# ESP01_SMD_0603.net
KiCad netlist of a schematic drawn in EAGLE
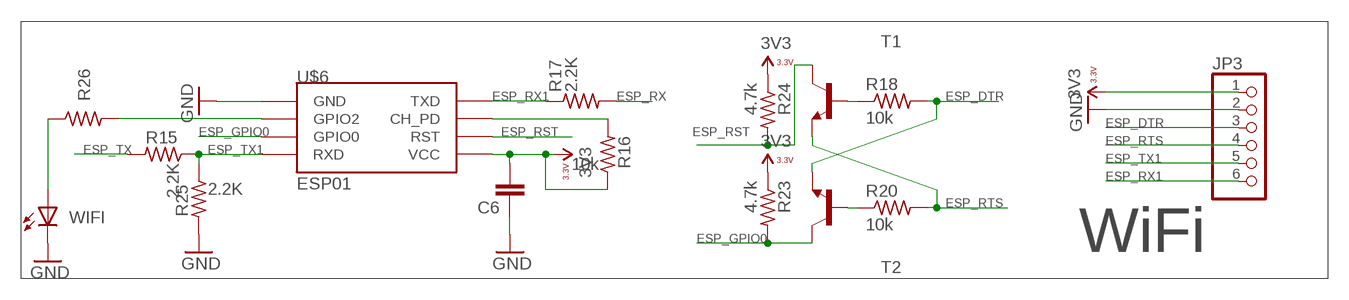
[diagram p0: schematic, sheet 1]

(export (version "E")
  (design (tool "Eeschema 10.0.6"))
  (components
    (comp (ref "C6")
      (value "C-EU050-024X044")
      (footprint "eagle-import:C050-024X044")
      (libsource (lib "eagle-import") (part "C-EU050-024X044"))
    )
    (comp (ref "JP3")
      (value "PINHD-1X6")
      (footprint "eagle-import:1X06")
      (libsource (lib "eagle-import") (part "PINHD-1X6"))
    )
    (comp (ref "R15")
      (value "2.2K")
      (footprint "eagle-import:R0603")
      (libsource (lib "eagle-import") (part "R-US_R0603"))
    )
    (comp (ref "R16")
      (value "10k")
      (footprint "eagle-import:R0603")
      (libsource (lib "eagle-import") (part "R-US_R0603"))
    )
    (comp (ref "R17")
      (value "2.2K")
      (footprint "eagle-import:R0603")
      (libsource (lib "eagle-import") (part "R-US_R0603"))
    )
    (comp (ref "R18")
      (value "10k")
      (footprint "eagle-import:R0603")
      (libsource (lib "eagle-import") (part "R-US_R0603"))
    )
    (comp (ref "R20")
      (value "10k")
      (footprint "eagle-import:R0603")
      (libsource (lib "eagle-import") (part "R-US_R0603"))
    )
    (comp (ref "R23")
      (value "4.7k")
      (footprint "eagle-import:R0603")
      (libsource (lib "eagle-import") (part "R-US_R0603"))
    )
    (comp (ref "R24")
      (value "4.7k")
      (footprint "eagle-import:R0603")
      (libsource (lib "eagle-import") (part "R-US_R0603"))
    )
    (comp (ref "R25")
      (value "2.2K")
      (footprint "eagle-import:R0603")
      (libsource (lib "eagle-import") (part "R-US_R0603"))
    )
    (comp (ref "R26")
      (value "R-US_R0603")
      (footprint "eagle-import:R0603")
      (libsource (lib "eagle-import") (part "R-US_R0603"))
    )
    (comp (ref "T1")
      (value "MMBT2222ALT1-NPN-SOT23-BEC")
      (footprint "eagle-import:SOT23-BEC")
      (libsource (lib "eagle-import") (part "-NPN-SOT23-BECMMBT2222ALT1"))
    )
    (comp (ref "T2")
      (value "MMBT2222ALT1-NPN-SOT23-BEC")
      (footprint "eagle-import:SOT23-BEC")
      (libsource (lib "eagle-import") (part "-NPN-SOT23-BECMMBT2222ALT1"))
    )
    (comp (ref "U$6")
      (value "ESP01")
      (footprint "eagle-import:ESP01")
      (libsource (lib "eagle-import") (part "ESP01"))
    )
    (comp (ref "WIFI")
      (value "LEDCHIPLED_0603")
      (footprint "eagle-import:CHIPLED_0603")
      (libsource (lib "eagle-import") (part "LEDCHIPLED_0603"))
    )
  )
  (nets
    (net (code "1") (name "/ESP_DTR") (class "Default")
      (node (ref "JP3") (pin "3") (pinfunction "3_3") (pintype "passive"))
      (node (ref "R18") (pin "2") (pinfunction "2_2") (pintype "passive"))
      (node (ref "T2") (pin "E") (pinfunction "E_E") (pintype "passive"))
    )
    (net (code "2") (name "/ESP_GPIO0") (class "Default")
      (node (ref "R23") (pin "2") (pinfunction "2_2") (pintype "passive"))
      (node (ref "T2") (pin "C") (pinfunction "C_C") (pintype "passive"))
      (node (ref "U$6") (pin "GPIO0") (pinfunction "GPIO0_GPIO0") (pintype "bidirectional"))
    )
    (net (code "3") (name "/ESP_RST") (class "Default")
      (node (ref "R24") (pin "2") (pinfunction "2_2") (pintype "passive"))
      (node (ref "T1") (pin "C") (pinfunction "C_C") (pintype "passive"))
      (node (ref "U$6") (pin "RST") (pinfunction "RST_RST") (pintype "bidirectional"))
    )
    (net (code "4") (name "/ESP_RTS") (class "Default")
      (node (ref "JP3") (pin "4") (pinfunction "4_4") (pintype "passive"))
      (node (ref "R20") (pin "2") (pinfunction "2_2") (pintype "passive"))
      (node (ref "T1") (pin "E") (pinfunction "E_E") (pintype "passive"))
    )
    (net (code "5") (name "/ESP_RX") (class "Default")
      (node (ref "R17") (pin "2") (pinfunction "2_2") (pintype "passive"))
    )
    (net (code "6") (name "/ESP_RX1") (class "Default")
      (node (ref "JP3") (pin "6") (pinfunction "6_6") (pintype "passive"))
      (node (ref "R17") (pin "1") (pinfunction "1_1") (pintype "passive"))
      (node (ref "U$6") (pin "TX") (pinfunction "TXD_TX") (pintype "bidirectional"))
    )
    (net (code "7") (name "/ESP_TX") (class "Default")
      (node (ref "R15") (pin "2") (pinfunction "2_2") (pintype "passive"))
    )
    (net (code "8") (name "/ESP_TX1") (class "Default")
      (node (ref "JP3") (pin "5") (pinfunction "5_5") (pintype "passive"))
      (node (ref "R15") (pin "1") (pinfunction "1_1") (pintype "passive"))
      (node (ref "R25") (pin "1") (pinfunction "1_1") (pintype "passive"))
      (node (ref "U$6") (pin "RX") (pinfunction "RXD_RX") (pintype "bidirectional"))
    )
    (net (code "9") (name "3V3") (class "Default")
      (node (ref "C6") (pin "2") (pinfunction "2_2") (pintype "passive"))
      (node (ref "JP3") (pin "1") (pinfunction "1_1") (pintype "passive"))
      (node (ref "R16") (pin "1") (pinfunction "1_1") (pintype "passive"))
      (node (ref "R23") (pin "1") (pinfunction "1_1") (pintype "passive"))
      (node (ref "R24") (pin "1") (pinfunction "1_1") (pintype "passive"))
      (node (ref "U$6") (pin "VCC") (pinfunction "VCC_VCC") (pintype "bidirectional"))
    )
    (net (code "10") (name "GND") (class "Default")
      (node (ref "C6") (pin "1") (pinfunction "1_1") (pintype "passive"))
      (node (ref "JP3") (pin "2") (pinfunction "2_2") (pintype "passive"))
      (node (ref "R25") (pin "2") (pinfunction "2_2") (pintype "passive"))
      (node (ref "U$6") (pin "GND") (pinfunction "GND_GND") (pintype "bidirectional"))
      (node (ref "WIFI") (pin "C") (pinfunction "C_C") (pintype "passive"))
    )
    (net (code "11") (name "Net-(R16-Pad2)") (class "Default")
      (node (ref "R16") (pin "2") (pinfunction "2_2") (pintype "passive"))
      (node (ref "U$6") (pin "CH_PD") (pinfunction "CH_PD_CH_PD") (pintype "bidirectional"))
    )
    (net (code "12") (name "Net-(R18-Pad1)") (class "Default")
      (node (ref "R18") (pin "1") (pinfunction "1_1") (pintype "passive"))
      (node (ref "T1") (pin "B") (pinfunction "B_B") (pintype "passive"))
    )
    (net (code "13") (name "Net-(R20-Pad1)") (class "Default")
      (node (ref "R20") (pin "1") (pinfunction "1_1") (pintype "passive"))
      (node (ref "T2") (pin "B") (pinfunction "B_B") (pintype "passive"))
    )
    (net (code "14") (name "Net-(R26-Pad1)") (class "Default")
      (node (ref "R26") (pin "1") (pinfunction "1_1") (pintype "passive"))
      (node (ref "WIFI") (pin "A") (pinfunction "A_A") (pintype "passive"))
    )
    (net (code "15") (name "Net-(R26-Pad2)") (class "Default")
      (node (ref "R26") (pin "2") (pinfunction "2_2") (pintype "passive"))
      (node (ref "U$6") (pin "GPIO2") (pinfunction "GPIO2_GPIO2") (pintype "bidirectional"))
    )
  )
)
